# POWER.net
KiCad netlist of a schematic drawn in Altium Designer
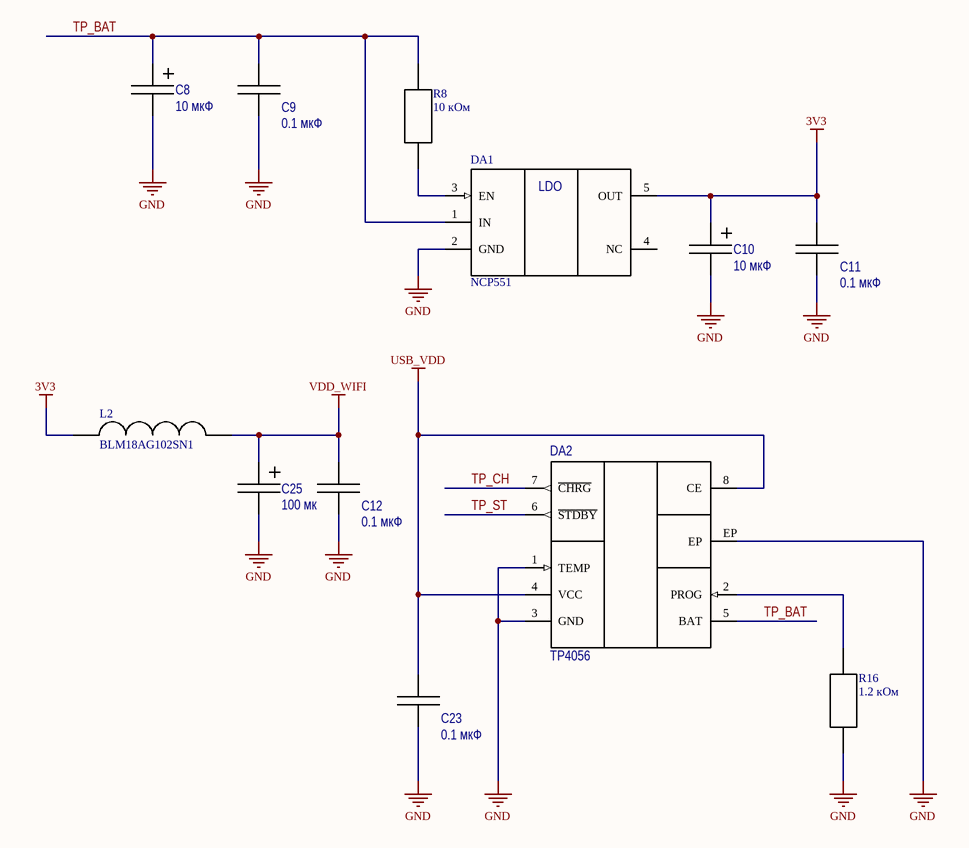
[diagram p0: POWER.SchDoc]

(export (version "E")
  (design (tool "Eeschema 10.0.6"))
  (components
    (comp (ref "C8")
      (value "10 мкФ")
      (footprint "C TAN_C")
      (description "SMD Tantalium Capacitor C")
      (fields
        (field (name "TOLERANCE") "/Укажите допуск в процентах/")
        (field (name "MANUFACTURER") "/Укажите компанию-производителя/")
      )
      (libsource (lib "my_lib") (part "CAP TAN_C"))
    )
    (comp (ref "C9")
      (value "0.1 мкФ")
      (footprint "C 1206")
      (description "SMD Capacitor 1206")
      (fields
        (field (name "TOLERANCE") "/Укажите допуск в процентах/")
        (field (name "MANUFACTURER") "/Укажите компанию-производителя/")
      )
      (libsource (lib "my_lib") (part "CAP 1206"))
    )
    (comp (ref "C10")
      (value "10 мкФ")
      (footprint "C TAN_C")
      (description "SMD Tantalium Capacitor C")
      (fields
        (field (name "TOLERANCE") "/Укажите допуск в процентах/")
        (field (name "MANUFACTURER") "/Укажите компанию-производителя/")
      )
      (libsource (lib "my_lib") (part "CAP TAN_C"))
    )
    (comp (ref "C11")
      (value "0.1 мкФ")
      (footprint "C 1206")
      (description "SMD Capacitor 1206")
      (fields
        (field (name "TOLERANCE") "/Укажите допуск в процентах/")
        (field (name "MANUFACTURER") "/Укажите компанию-производителя/")
      )
      (libsource (lib "my_lib") (part "CAP 1206"))
    )
    (comp (ref "C12")
      (value "0.1 мкФ")
      (footprint "C 1206")
      (description "SMD Capacitor 1206")
      (fields
        (field (name "TOLERANCE") "/Укажите допуск в процентах/")
        (field (name "MANUFACTURER") "/Укажите компанию-производителя/")
      )
      (libsource (lib "my_lib") (part "CAP 1206"))
    )
    (comp (ref "C23")
      (value "0.1 мкФ")
      (footprint "C 1206")
      (description "SMD Capacitor 1206")
      (fields
        (field (name "TOLERANCE") "/Укажите допуск в процентах/")
        (field (name "MANUFACTURER") "/Укажите компанию-производителя/")
      )
      (libsource (lib "my_lib") (part "CAP 1206"))
    )
    (comp (ref "C25")
      (value "100 мк")
      (footprint "C TAN_D")
      (description "SMD Tantalium Capacitor D")
      (fields
        (field (name "TOLERANCE") "/Укажите допуск в процентах/")
        (field (name "MANUFACTURER") "/Укажите компанию-производителя/")
      )
      (libsource (lib "my_lib") (part "CAP TAN_D"))
    )
    (comp (ref "DA1") (value "NCP551") (footprint "TSOP-5") (libsource (lib "my_lib") (part "NCP551")))
    (comp (ref "DA2") (value "TP4056") (footprint "HSOP-8") (libsource (lib "my_lib") (part "TP4056")))
    (comp (ref "L2")
      (value "BLM18AG102SN1")
      (footprint "FB 0603")
      (libsource (lib "my_lib") (part "BLM18AG102SN1"))
    )
    (comp (ref "R8") (value "10 кОм") (footprint "RES 0805") (libsource (lib "my_lib") (part "RES 0805")))
    (comp (ref "R16") (value "1.2 кОм") (footprint "RES 0805") (libsource (lib "my_lib") (part "RES 0805")))
  )
  (nets
    (net (code "1") (name "/TP_BAT") (class "Default")
      (node (ref "C8") (pin "1") (pinfunction "1_1") (pintype "passive"))
      (node (ref "C9") (pin "1") (pinfunction "1_1") (pintype "passive"))
      (node (ref "DA1") (pin "1") (pinfunction "IN_1") (pintype "passive"))
      (node (ref "DA2") (pin "5") (pinfunction "BAT_5") (pintype "power_in"))
      (node (ref "R8") (pin "2") (pinfunction "2_2") (pintype "passive"))
    )
    (net (code "2") (name "/TP_CH") (class "Default")
      (node (ref "DA2") (pin "7") (pinfunction "~{CHRG}_7") (pintype "output"))
    )
    (net (code "3") (name "/TP_ST") (class "Default")
      (node (ref "DA2") (pin "6") (pinfunction "~{STDBY}_6") (pintype "output"))
    )
    (net (code "4") (name "3V3") (class "Default")
      (node (ref "C10") (pin "1") (pinfunction "1_1") (pintype "passive"))
      (node (ref "C11") (pin "1") (pinfunction "1_1") (pintype "passive"))
      (node (ref "DA1") (pin "5") (pinfunction "OUT_5") (pintype "passive"))
      (node (ref "L2") (pin "1") (pinfunction "1_1") (pintype "passive"))
    )
    (net (code "5") (name "GND") (class "Default")
      (node (ref "C10") (pin "2") (pinfunction "2_2") (pintype "passive"))
      (node (ref "C11") (pin "2") (pinfunction "2_2") (pintype "passive"))
      (node (ref "C12") (pin "2") (pinfunction "2_2") (pintype "passive"))
      (node (ref "C23") (pin "2") (pinfunction "2_2") (pintype "passive"))
      (node (ref "C25") (pin "2") (pinfunction "2_2") (pintype "passive"))
      (node (ref "C8") (pin "2") (pinfunction "2_2") (pintype "passive"))
      (node (ref "C9") (pin "2") (pinfunction "2_2") (pintype "passive"))
      (node (ref "DA1") (pin "2") (pinfunction "GND_2") (pintype "passive"))
      (node (ref "DA2") (pin "1") (pinfunction "TEMP_1") (pintype "input"))
      (node (ref "DA2") (pin "3") (pinfunction "GND_3") (pintype "power_in"))
      (node (ref "DA2") (pin "EP") (pinfunction "EP_EP") (pintype "passive"))
      (node (ref "R16") (pin "1") (pinfunction "1_1") (pintype "passive"))
    )
    (net (code "6") (name "Net-(DA1-EN)") (class "Default")
      (node (ref "DA1") (pin "3") (pinfunction "EN_3") (pintype "input"))
      (node (ref "R8") (pin "1") (pinfunction "1_1") (pintype "passive"))
    )
    (net (code "7") (name "Net-(DA2-PROG)") (class "Default")
      (node (ref "DA2") (pin "2") (pinfunction "PROG_2") (pintype "input"))
      (node (ref "R16") (pin "2") (pinfunction "2_2") (pintype "passive"))
    )
    (net (code "8") (name "USB_VDD") (class "Default")
      (node (ref "C23") (pin "1") (pinfunction "1_1") (pintype "passive"))
      (node (ref "DA2") (pin "4") (pinfunction "VCC_4") (pintype "power_in"))
      (node (ref "DA2") (pin "8") (pinfunction "CE_8") (pintype "passive"))
    )
    (net (code "9") (name "VDD_WIFI") (class "Default")
      (node (ref "C12") (pin "1") (pinfunction "1_1") (pintype "passive"))
      (node (ref "C25") (pin "1") (pinfunction "1_1") (pintype "passive"))
      (node (ref "L2") (pin "2") (pinfunction "2_2") (pintype "passive"))
    )
    (net (code "10") (name "unconnected-(DA1-NC-Pad4)") (class "Default")
      (node (ref "DA1") (pin "4") (pinfunction "NC_4") (pintype "passive"))
    )
  )
)
